# mcp30008.net
KiCad netlist of a schematic drawn in EAGLE
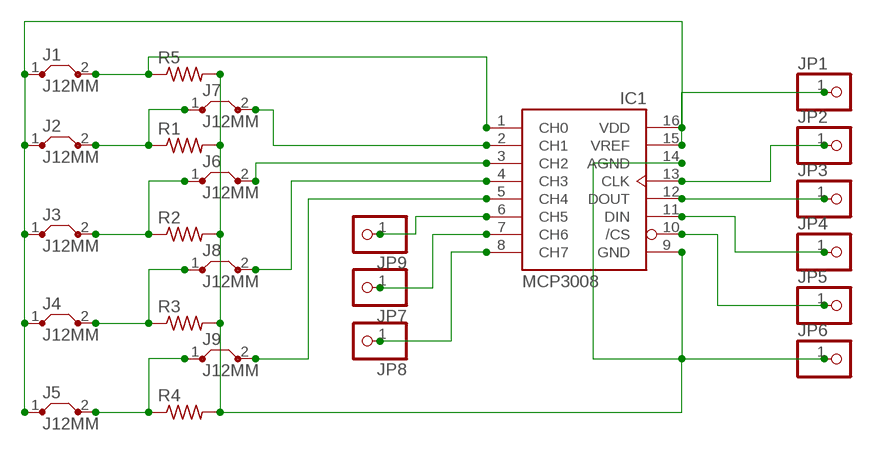
[diagram p0: schematic, sheet 1]

(export (version "E")
  (design (tool "Eeschema 10.0.6"))
  (components
    (comp (ref "IC1")
      (value "MCP3008")
      (footprint "eagle-import:DIL16")
      (libsource (lib "eagle-import") (part "MCP3008"))
    )
    (comp (ref "J1")
      (value "J12MM")
      (footprint "eagle-import:12")
      (libsource (lib "eagle-import") (part "J12MM"))
    )
    (comp (ref "J2")
      (value "J12MM")
      (footprint "eagle-import:12")
      (libsource (lib "eagle-import") (part "J12MM"))
    )
    (comp (ref "J3")
      (value "J12MM")
      (footprint "eagle-import:12")
      (libsource (lib "eagle-import") (part "J12MM"))
    )
    (comp (ref "J4")
      (value "J12MM")
      (footprint "eagle-import:12")
      (libsource (lib "eagle-import") (part "J12MM"))
    )
    (comp (ref "J5")
      (value "J12MM")
      (footprint "eagle-import:12")
      (libsource (lib "eagle-import") (part "J12MM"))
    )
    (comp (ref "J6")
      (value "J12MM")
      (footprint "eagle-import:12")
      (libsource (lib "eagle-import") (part "J12MM"))
    )
    (comp (ref "J7")
      (value "J12MM")
      (footprint "eagle-import:12")
      (libsource (lib "eagle-import") (part "J12MM"))
    )
    (comp (ref "J8")
      (value "J12MM")
      (footprint "eagle-import:12")
      (libsource (lib "eagle-import") (part "J12MM"))
    )
    (comp (ref "J9")
      (value "J12MM")
      (footprint "eagle-import:12")
      (libsource (lib "eagle-import") (part "J12MM"))
    )
    (comp (ref "JP1")
      (value "PINHD-1X1")
      (footprint "eagle-import:1X01")
      (libsource (lib "eagle-import") (part "PINHD-1X1"))
    )
    (comp (ref "JP2")
      (value "PINHD-1X1")
      (footprint "eagle-import:1X01")
      (libsource (lib "eagle-import") (part "PINHD-1X1"))
    )
    (comp (ref "JP3")
      (value "PINHD-1X1")
      (footprint "eagle-import:1X01")
      (libsource (lib "eagle-import") (part "PINHD-1X1"))
    )
    (comp (ref "JP4")
      (value "PINHD-1X1")
      (footprint "eagle-import:1X01")
      (libsource (lib "eagle-import") (part "PINHD-1X1"))
    )
    (comp (ref "JP5")
      (value "PINHD-1X1")
      (footprint "eagle-import:1X01")
      (libsource (lib "eagle-import") (part "PINHD-1X1"))
    )
    (comp (ref "JP6")
      (value "PINHD-1X1")
      (footprint "eagle-import:1X01")
      (libsource (lib "eagle-import") (part "PINHD-1X1"))
    )
    (comp (ref "JP7")
      (value "PINHD-1X1")
      (footprint "eagle-import:1X01")
      (libsource (lib "eagle-import") (part "PINHD-1X1"))
    )
    (comp (ref "JP8")
      (value "PINHD-1X1")
      (footprint "eagle-import:1X01")
      (libsource (lib "eagle-import") (part "PINHD-1X1"))
    )
    (comp (ref "JP9")
      (value "PINHD-1X1")
      (footprint "eagle-import:1X01")
      (libsource (lib "eagle-import") (part "PINHD-1X1"))
    )
    (comp (ref "R1")
      (value "R-US_0207/15")
      (footprint "eagle-import:0207_15")
      (libsource (lib "eagle-import") (part "R-US_0207/15"))
    )
    (comp (ref "R2")
      (value "R-US_0207/15")
      (footprint "eagle-import:0207_15")
      (libsource (lib "eagle-import") (part "R-US_0207/15"))
    )
    (comp (ref "R3")
      (value "R-US_0207/15")
      (footprint "eagle-import:0207_15")
      (libsource (lib "eagle-import") (part "R-US_0207/15"))
    )
    (comp (ref "R4")
      (value "R-US_0207/15")
      (footprint "eagle-import:0207_15")
      (libsource (lib "eagle-import") (part "R-US_0207/15"))
    )
    (comp (ref "R5")
      (value "R-US_0207/15")
      (footprint "eagle-import:0207_15")
      (libsource (lib "eagle-import") (part "R-US_0207/15"))
    )
  )
  (nets
    (net (code "1") (name "Net-(IC1-AGND)") (class "Default")
      (node (ref "IC1") (pin "14") (pinfunction "AGND_14") (pintype "power_in"))
      (node (ref "IC1") (pin "9") (pinfunction "GND_9") (pintype "power_in"))
      (node (ref "JP6") (pin "1") (pinfunction "1_1") (pintype "passive"))
      (node (ref "R1") (pin "2") (pinfunction "2_2") (pintype "passive"))
      (node (ref "R2") (pin "2") (pinfunction "2_2") (pintype "passive"))
      (node (ref "R3") (pin "2") (pinfunction "2_2") (pintype "passive"))
      (node (ref "R4") (pin "2") (pinfunction "2_2") (pintype "passive"))
      (node (ref "R5") (pin "2") (pinfunction "2_2") (pintype "passive"))
    )
    (net (code "2") (name "Net-(IC1-CH0)") (class "Default")
      (node (ref "IC1") (pin "1") (pinfunction "CH0_1") (pintype "input"))
      (node (ref "J1") (pin "2") (pinfunction "2_2") (pintype "passive"))
      (node (ref "R5") (pin "1") (pinfunction "1_1") (pintype "passive"))
    )
    (net (code "3") (name "Net-(IC1-CH1)") (class "Default")
      (node (ref "IC1") (pin "2") (pinfunction "CH1_2") (pintype "input"))
      (node (ref "J7") (pin "2") (pinfunction "2_2") (pintype "passive"))
    )
    (net (code "4") (name "Net-(IC1-CH2)") (class "Default")
      (node (ref "IC1") (pin "3") (pinfunction "CH2_3") (pintype "input"))
      (node (ref "J6") (pin "2") (pinfunction "2_2") (pintype "passive"))
    )
    (net (code "5") (name "Net-(IC1-CH3)") (class "Default")
      (node (ref "IC1") (pin "4") (pinfunction "CH3_4") (pintype "input"))
      (node (ref "J8") (pin "2") (pinfunction "2_2") (pintype "passive"))
    )
    (net (code "6") (name "Net-(IC1-CH4)") (class "Default")
      (node (ref "IC1") (pin "5") (pinfunction "CH4_5") (pintype "input"))
      (node (ref "J9") (pin "2") (pinfunction "2_2") (pintype "passive"))
    )
    (net (code "7") (name "Net-(IC1-CH5)") (class "Default")
      (node (ref "IC1") (pin "6") (pinfunction "CH5_6") (pintype "input"))
      (node (ref "JP9") (pin "1") (pinfunction "1_1") (pintype "passive"))
    )
    (net (code "8") (name "Net-(IC1-CH6)") (class "Default")
      (node (ref "IC1") (pin "7") (pinfunction "CH6_7") (pintype "input"))
      (node (ref "JP7") (pin "1") (pinfunction "1_1") (pintype "passive"))
    )
    (net (code "9") (name "Net-(IC1-CH7)") (class "Default")
      (node (ref "IC1") (pin "8") (pinfunction "CH7_8") (pintype "input"))
      (node (ref "JP8") (pin "1") (pinfunction "1_1") (pintype "passive"))
    )
    (net (code "10") (name "Net-(IC1-CLK)") (class "Default")
      (node (ref "IC1") (pin "13") (pinfunction "CLK_13") (pintype "input"))
      (node (ref "JP2") (pin "1") (pinfunction "1_1") (pintype "passive"))
    )
    (net (code "11") (name "Net-(IC1-DIN)") (class "Default")
      (node (ref "IC1") (pin "11") (pinfunction "DIN_11") (pintype "input"))
      (node (ref "JP4") (pin "1") (pinfunction "1_1") (pintype "passive"))
    )
    (net (code "12") (name "Net-(IC1-DOUT)") (class "Default")
      (node (ref "IC1") (pin "12") (pinfunction "DOUT_12") (pintype "output"))
      (node (ref "JP3") (pin "1") (pinfunction "1_1") (pintype "passive"))
    )
    (net (code "13") (name "Net-(IC1-VDD)") (class "Default")
      (node (ref "IC1") (pin "15") (pinfunction "VREF_15") (pintype "input"))
      (node (ref "IC1") (pin "16") (pinfunction "VDD_16") (pintype "power_in"))
      (node (ref "J1") (pin "1") (pinfunction "1_1") (pintype "passive"))
      (node (ref "J2") (pin "1") (pinfunction "1_1") (pintype "passive"))
      (node (ref "J3") (pin "1") (pinfunction "1_1") (pintype "passive"))
      (node (ref "J4") (pin "1") (pinfunction "1_1") (pintype "passive"))
      (node (ref "J5") (pin "1") (pinfunction "1_1") (pintype "passive"))
      (node (ref "JP1") (pin "1") (pinfunction "1_1") (pintype "passive"))
    )
    (net (code "14") (name "Net-(IC1-{slash}CS)") (class "Default")
      (node (ref "IC1") (pin "10") (pinfunction "/CS_10") (pintype "input"))
      (node (ref "JP5") (pin "1") (pinfunction "1_1") (pintype "passive"))
    )
    (net (code "15") (name "Net-(J2-Pad2)") (class "Default")
      (node (ref "J2") (pin "2") (pinfunction "2_2") (pintype "passive"))
      (node (ref "J7") (pin "1") (pinfunction "1_1") (pintype "passive"))
      (node (ref "R1") (pin "1") (pinfunction "1_1") (pintype "passive"))
    )
    (net (code "16") (name "Net-(J3-Pad2)") (class "Default")
      (node (ref "J3") (pin "2") (pinfunction "2_2") (pintype "passive"))
      (node (ref "J6") (pin "1") (pinfunction "1_1") (pintype "passive"))
      (node (ref "R2") (pin "1") (pinfunction "1_1") (pintype "passive"))
    )
    (net (code "17") (name "Net-(J4-Pad2)") (class "Default")
      (node (ref "J4") (pin "2") (pinfunction "2_2") (pintype "passive"))
      (node (ref "J8") (pin "1") (pinfunction "1_1") (pintype "passive"))
      (node (ref "R3") (pin "1") (pinfunction "1_1") (pintype "passive"))
    )
    (net (code "18") (name "Net-(J5-Pad2)") (class "Default")
      (node (ref "J5") (pin "2") (pinfunction "2_2") (pintype "passive"))
      (node (ref "J9") (pin "1") (pinfunction "1_1") (pintype "passive"))
      (node (ref "R4") (pin "1") (pinfunction "1_1") (pintype "passive"))
    )
  )
)
